# OpenHealth_rj45v2.net
KiCad netlist of a schematic drawn in EAGLE
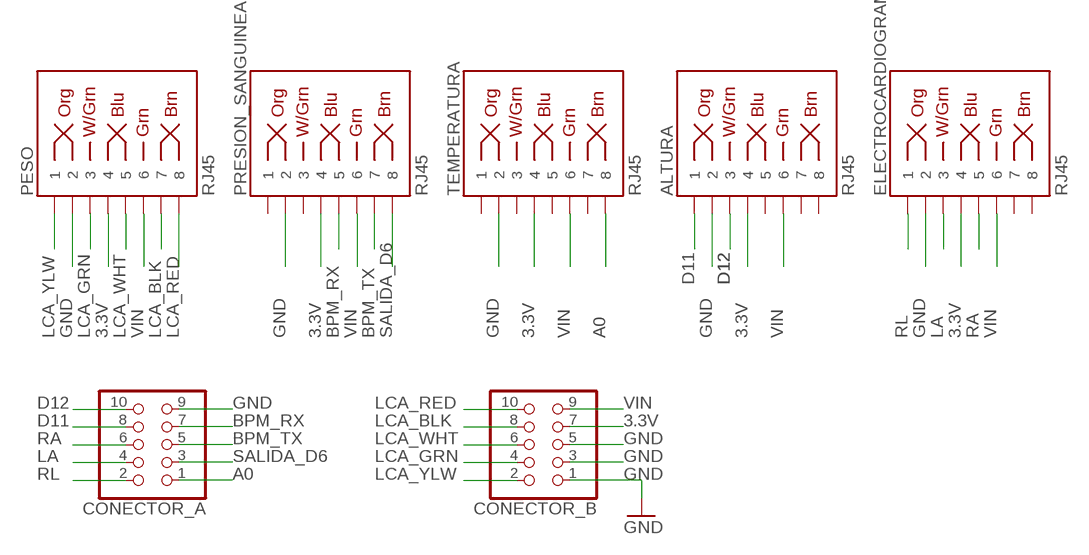
[diagram p0: schematic, sheet 1]

(export (version "E")
  (design (tool "Eeschema 10.0.6"))
  (components
    (comp (ref "ALTURA")
      (value "RJ45")
      (footprint "eagle-import:RJ45-8")
      (libsource (lib "eagle-import") (part "RJ45-8PTH"))
    )
    (comp (ref "CONECTOR_A")
      (value "PINHD-2X5")
      (footprint "eagle-import:2X05")
      (libsource (lib "eagle-import") (part "PINHD-2X5"))
    )
    (comp (ref "CONECTOR_B")
      (value "PINHD-2X5")
      (footprint "eagle-import:2X05")
      (libsource (lib "eagle-import") (part "PINHD-2X5"))
    )
    (comp (ref "ELECTROCARDIOGRAMA")
      (value "RJ45")
      (footprint "eagle-import:RJ45-8")
      (libsource (lib "eagle-import") (part "RJ45-8PTH"))
    )
    (comp (ref "PESO")
      (value "RJ45")
      (footprint "eagle-import:RJ45-8")
      (libsource (lib "eagle-import") (part "RJ45-8PTH"))
    )
    (comp (ref "PRESION_SANGUINEA")
      (value "RJ45")
      (footprint "eagle-import:RJ45-8")
      (libsource (lib "eagle-import") (part "RJ45-8PTH"))
    )
    (comp (ref "TEMPERATURA")
      (value "RJ45")
      (footprint "eagle-import:RJ45-8")
      (libsource (lib "eagle-import") (part "RJ45-8PTH"))
    )
  )
  (nets
    (net (code "1") (name "/3.3V") (class "Default")
      (node (ref "ALTURA") (pin "4") (pinfunction "4_4") (pintype "bidirectional"))
      (node (ref "CONECTOR_B") (pin "7") (pinfunction "7_7") (pintype "passive"))
      (node (ref "ELECTROCARDIOGRAMA") (pin "4") (pinfunction "4_4") (pintype "bidirectional"))
      (node (ref "PESO") (pin "4") (pinfunction "4_4") (pintype "bidirectional"))
      (node (ref "PRESION_SANGUINEA") (pin "4") (pinfunction "4_4") (pintype "bidirectional"))
      (node (ref "TEMPERATURA") (pin "4") (pinfunction "4_4") (pintype "bidirectional"))
    )
    (net (code "2") (name "/A0") (class "Default")
      (node (ref "CONECTOR_A") (pin "1") (pinfunction "1_1") (pintype "passive"))
      (node (ref "TEMPERATURA") (pin "8") (pinfunction "8_8") (pintype "bidirectional"))
    )
    (net (code "3") (name "/BPM_RX") (class "Default")
      (node (ref "CONECTOR_A") (pin "7") (pinfunction "7_7") (pintype "passive"))
      (node (ref "PRESION_SANGUINEA") (pin "5") (pinfunction "5_5") (pintype "bidirectional"))
    )
    (net (code "4") (name "/BPM_TX") (class "Default")
      (node (ref "CONECTOR_A") (pin "5") (pinfunction "5_5") (pintype "passive"))
      (node (ref "PRESION_SANGUINEA") (pin "7") (pinfunction "7_7") (pintype "bidirectional"))
    )
    (net (code "5") (name "/D11") (class "Default")
      (node (ref "ALTURA") (pin "1") (pinfunction "1_1") (pintype "bidirectional"))
      (node (ref "CONECTOR_A") (pin "8") (pinfunction "8_8") (pintype "passive"))
    )
    (net (code "6") (name "/D12") (class "Default")
      (node (ref "ALTURA") (pin "3") (pinfunction "3_3") (pintype "bidirectional"))
      (node (ref "CONECTOR_A") (pin "10") (pinfunction "10_10") (pintype "passive"))
    )
    (net (code "7") (name "/LA") (class "Default")
      (node (ref "CONECTOR_A") (pin "4") (pinfunction "4_4") (pintype "passive"))
      (node (ref "ELECTROCARDIOGRAMA") (pin "3") (pinfunction "3_3") (pintype "bidirectional"))
    )
    (net (code "8") (name "/LCA_BLK") (class "Default")
      (node (ref "CONECTOR_B") (pin "8") (pinfunction "8_8") (pintype "passive"))
      (node (ref "PESO") (pin "7") (pinfunction "7_7") (pintype "bidirectional"))
    )
    (net (code "9") (name "/LCA_GRN") (class "Default")
      (node (ref "CONECTOR_B") (pin "4") (pinfunction "4_4") (pintype "passive"))
      (node (ref "PESO") (pin "3") (pinfunction "3_3") (pintype "bidirectional"))
    )
    (net (code "10") (name "/LCA_RED") (class "Default")
      (node (ref "CONECTOR_B") (pin "10") (pinfunction "10_10") (pintype "passive"))
      (node (ref "PESO") (pin "8") (pinfunction "8_8") (pintype "bidirectional"))
    )
    (net (code "11") (name "/LCA_WHT") (class "Default")
      (node (ref "CONECTOR_B") (pin "6") (pinfunction "6_6") (pintype "passive"))
      (node (ref "PESO") (pin "5") (pinfunction "5_5") (pintype "bidirectional"))
    )
    (net (code "12") (name "/LCA_YLW") (class "Default")
      (node (ref "CONECTOR_B") (pin "2") (pinfunction "2_2") (pintype "passive"))
      (node (ref "PESO") (pin "1") (pinfunction "1_1") (pintype "bidirectional"))
    )
    (net (code "13") (name "/RA") (class "Default")
      (node (ref "CONECTOR_A") (pin "6") (pinfunction "6_6") (pintype "passive"))
      (node (ref "ELECTROCARDIOGRAMA") (pin "5") (pinfunction "5_5") (pintype "bidirectional"))
    )
    (net (code "14") (name "/RL") (class "Default")
      (node (ref "CONECTOR_A") (pin "2") (pinfunction "2_2") (pintype "passive"))
      (node (ref "ELECTROCARDIOGRAMA") (pin "1") (pinfunction "1_1") (pintype "bidirectional"))
    )
    (net (code "15") (name "/SALIDA_D6") (class "Default")
      (node (ref "CONECTOR_A") (pin "3") (pinfunction "3_3") (pintype "passive"))
      (node (ref "PRESION_SANGUINEA") (pin "8") (pinfunction "8_8") (pintype "bidirectional"))
    )
    (net (code "16") (name "/VIN") (class "Default")
      (node (ref "ALTURA") (pin "6") (pinfunction "6_6") (pintype "bidirectional"))
      (node (ref "CONECTOR_B") (pin "9") (pinfunction "9_9") (pintype "passive"))
      (node (ref "ELECTROCARDIOGRAMA") (pin "6") (pinfunction "6_6") (pintype "bidirectional"))
      (node (ref "PESO") (pin "6") (pinfunction "6_6") (pintype "bidirectional"))
      (node (ref "PRESION_SANGUINEA") (pin "6") (pinfunction "6_6") (pintype "bidirectional"))
      (node (ref "TEMPERATURA") (pin "6") (pinfunction "6_6") (pintype "bidirectional"))
    )
    (net (code "17") (name "GND") (class "Default")
      (node (ref "ALTURA") (pin "2") (pinfunction "2_2") (pintype "bidirectional"))
      (node (ref "CONECTOR_A") (pin "9") (pinfunction "9_9") (pintype "passive"))
      (node (ref "CONECTOR_B") (pin "1") (pinfunction "1_1") (pintype "passive"))
      (node (ref "CONECTOR_B") (pin "3") (pinfunction "3_3") (pintype "passive"))
      (node (ref "CONECTOR_B") (pin "5") (pinfunction "5_5") (pintype "passive"))
      (node (ref "ELECTROCARDIOGRAMA") (pin "2") (pinfunction "2_2") (pintype "bidirectional"))
      (node (ref "PESO") (pin "2") (pinfunction "2_2") (pintype "bidirectional"))
      (node (ref "PRESION_SANGUINEA") (pin "2") (pinfunction "2_2") (pintype "bidirectional"))
      (node (ref "TEMPERATURA") (pin "2") (pinfunction "2_2") (pintype "bidirectional"))
    )
    (net (code "18") (name "unconnected-(ALTURA-Pad5)") (class "Default")
      (node (ref "ALTURA") (pin "5") (pinfunction "5_5") (pintype "bidirectional"))
    )
    (net (code "19") (name "unconnected-(ALTURA-Pad7)") (class "Default")
      (node (ref "ALTURA") (pin "7") (pinfunction "7_7") (pintype "bidirectional"))
    )
    (net (code "20") (name "unconnected-(ALTURA-Pad8)") (class "Default")
      (node (ref "ALTURA") (pin "8") (pinfunction "8_8") (pintype "bidirectional"))
    )
    (net (code "21") (name "unconnected-(ELECTROCARDIOGRAMA-Pad7)") (class "Default")
      (node (ref "ELECTROCARDIOGRAMA") (pin "7") (pinfunction "7_7") (pintype "bidirectional"))
    )
    (net (code "22") (name "unconnected-(ELECTROCARDIOGRAMA-Pad8)") (class "Default")
      (node (ref "ELECTROCARDIOGRAMA") (pin "8") (pinfunction "8_8") (pintype "bidirectional"))
    )
    (net (code "23") (name "unconnected-(PRESION_SANGUINEA-Pad1)") (class "Default")
      (node (ref "PRESION_SANGUINEA") (pin "1") (pinfunction "1_1") (pintype "bidirectional"))
    )
    (net (code "24") (name "unconnected-(PRESION_SANGUINEA-Pad3)") (class "Default")
      (node (ref "PRESION_SANGUINEA") (pin "3") (pinfunction "3_3") (pintype "bidirectional"))
    )
    (net (code "25") (name "unconnected-(TEMPERATURA-Pad1)") (class "Default")
      (node (ref "TEMPERATURA") (pin "1") (pinfunction "1_1") (pintype "bidirectional"))
    )
    (net (code "26") (name "unconnected-(TEMPERATURA-Pad3)") (class "Default")
      (node (ref "TEMPERATURA") (pin "3") (pinfunction "3_3") (pintype "bidirectional"))
    )
    (net (code "27") (name "unconnected-(TEMPERATURA-Pad5)") (class "Default")
      (node (ref "TEMPERATURA") (pin "5") (pinfunction "5_5") (pintype "bidirectional"))
    )
    (net (code "28") (name "unconnected-(TEMPERATURA-Pad7)") (class "Default")
      (node (ref "TEMPERATURA") (pin "7") (pinfunction "7_7") (pintype "bidirectional"))
    )
  )
)
